# Sheet1.net
KiCad netlist of a schematic drawn in Altium Designer
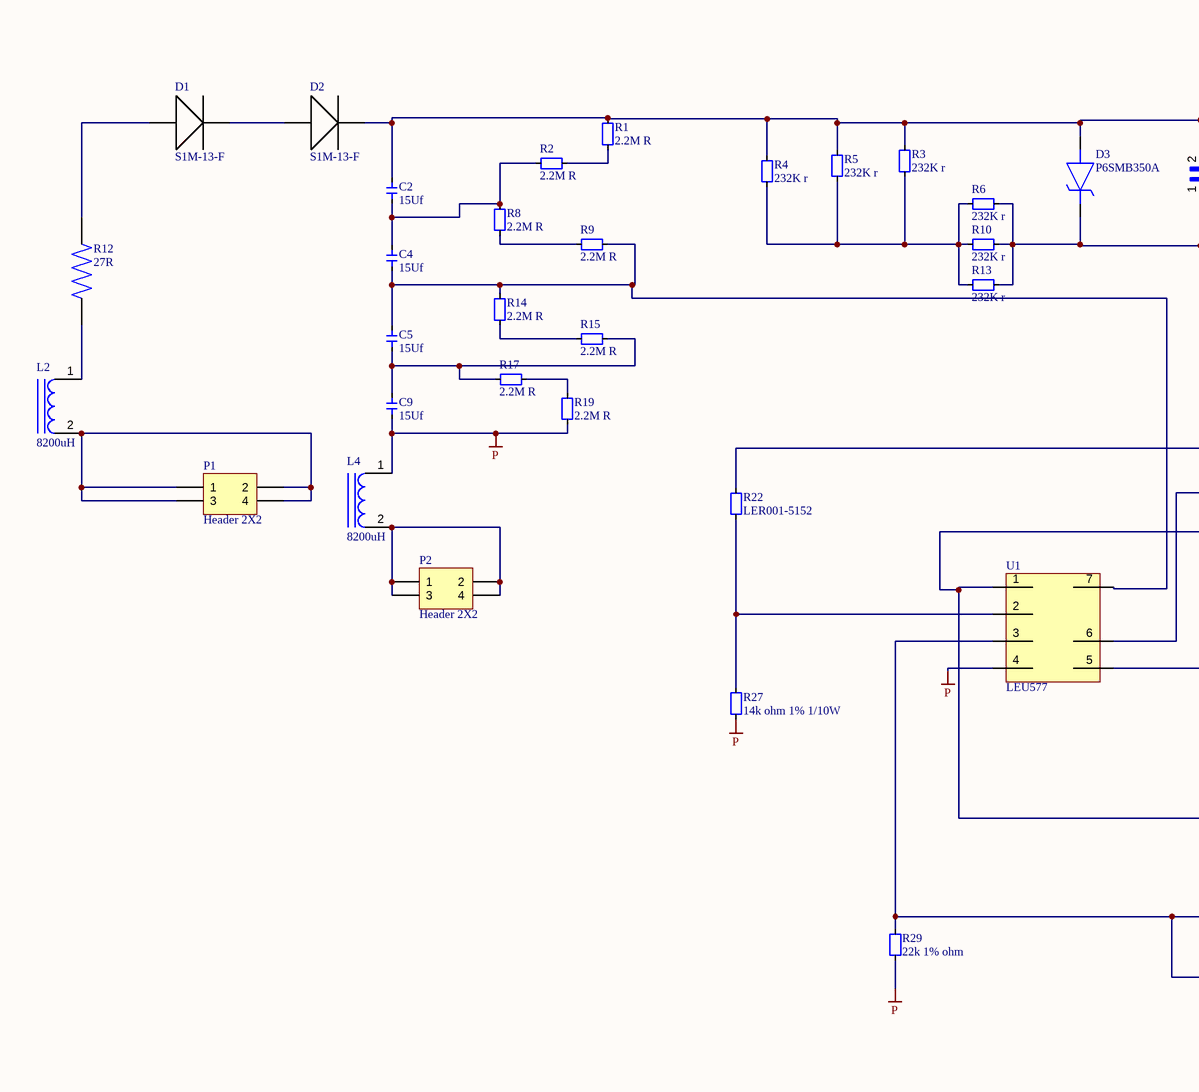
[diagram p0: Sheet1.SchDoc, left]
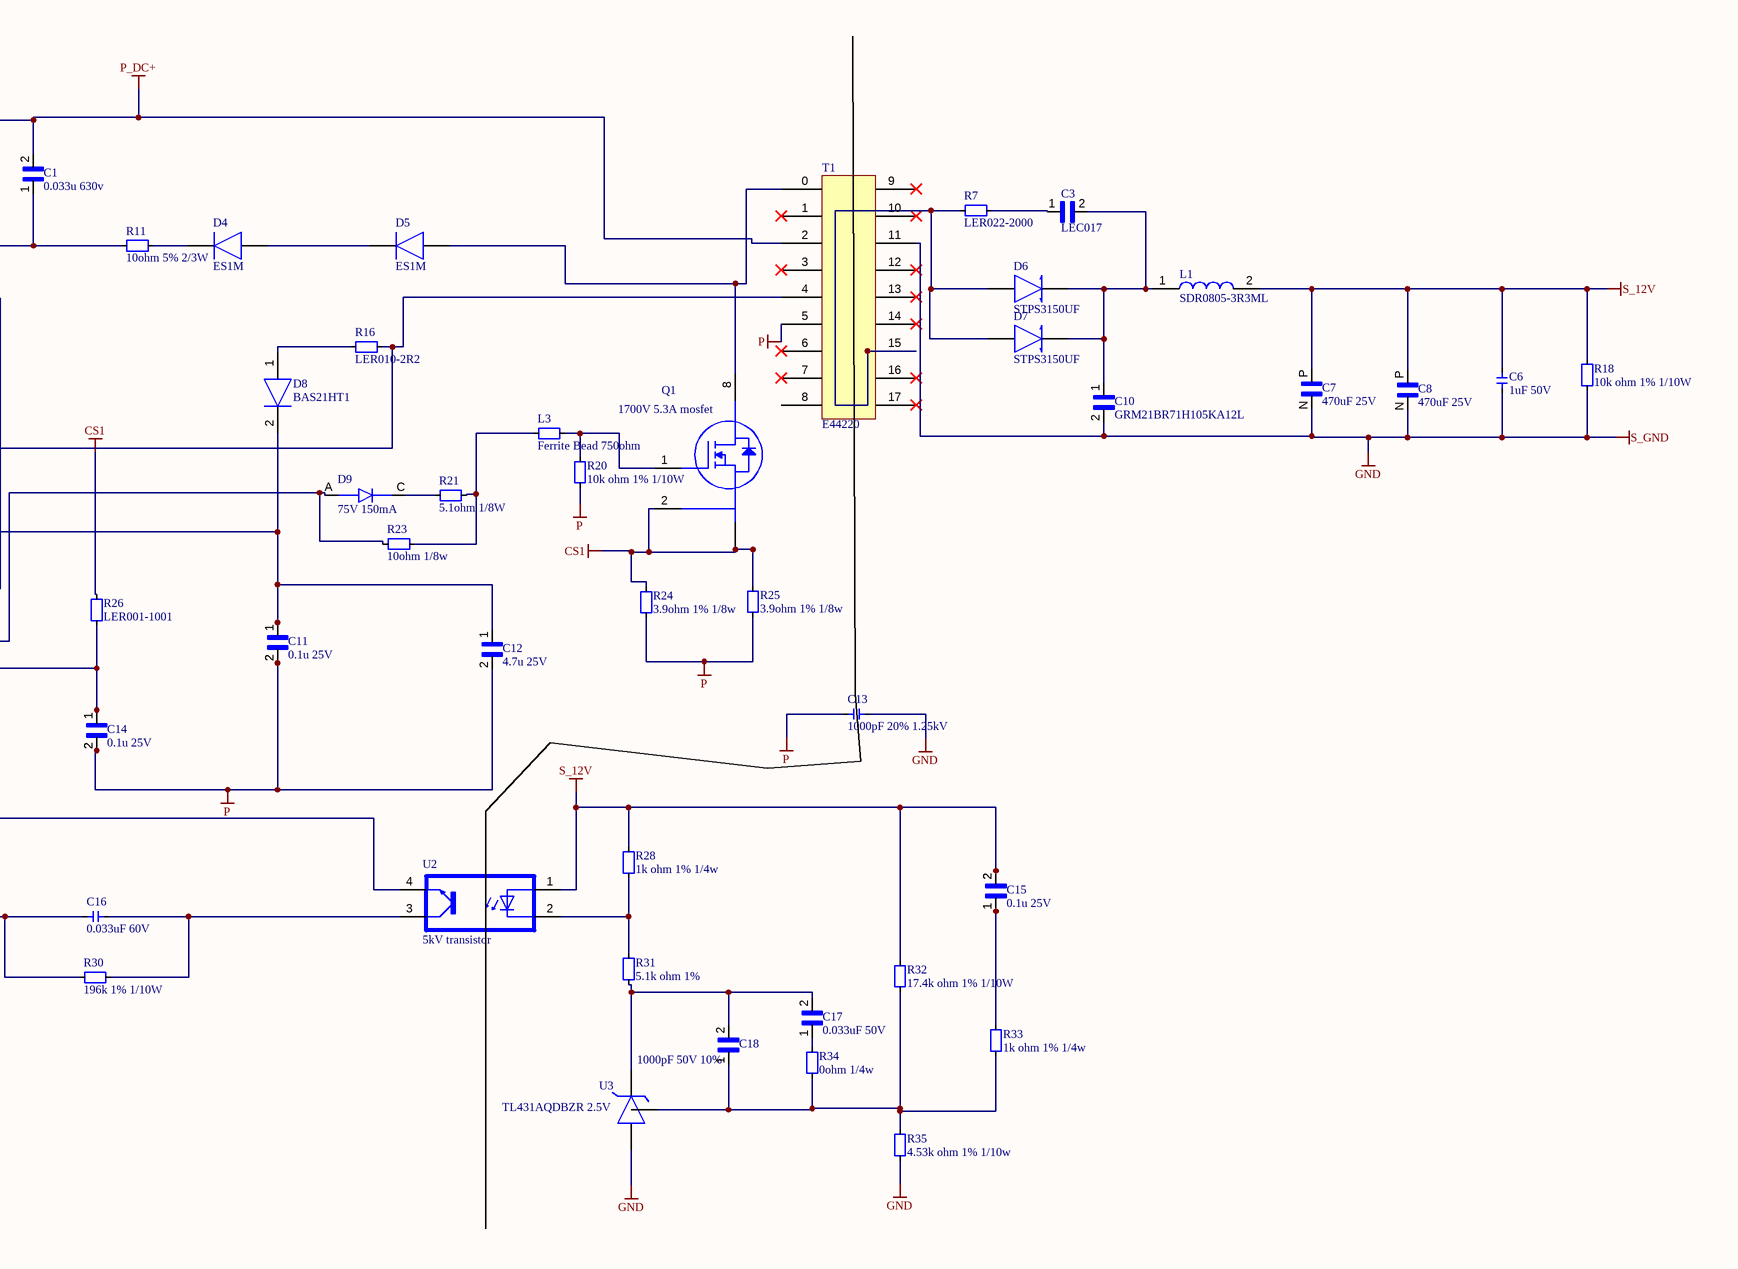
[diagram p1: Sheet1.SchDoc, right]

(export (version "E")
  (design (tool "Eeschema 10.0.6"))
  (components
    (comp (ref "C1")
      (value "0.033u 630v")
      (footprint "PcbLib1:0.33u 630V c")
      (libsource (lib "Schlib1") (part "0.033u 630v"))
    )
    (comp (ref "C2") (value "15Uf") (footprint "PcbLib1:15uf") (libsource (lib "Schlib1") (part "15Uf")))
    (comp (ref "C3")
      (value "LEC017")
      (footprint "PcbLib1:LEC017")
      (libsource (lib "Schlib1") (part "LEC017"))
    )
    (comp (ref "C4") (value "15Uf") (footprint "PcbLib1:15uf") (libsource (lib "Schlib1") (part "15Uf")))
    (comp (ref "C5") (value "15Uf") (footprint "PcbLib1:15uf") (libsource (lib "Schlib1") (part "15Uf")))
    (comp (ref "C6")
      (value "1uF 50V")
      (footprint "PcbLib1:C-0805")
      (libsource (lib "Schlib1") (part "1uF 50V"))
    )
    (comp (ref "C7")
      (value "470uF 25V")
      (footprint "470uF 25V")
      (libsource (lib "Schlib1") (part "470uF 25V"))
    )
    (comp (ref "C8")
      (value "470uF 25V")
      (footprint "470uF 25V")
      (libsource (lib "Schlib1") (part "470uF 25V"))
    )
    (comp (ref "C9") (value "15Uf") (footprint "PcbLib1:15uf") (libsource (lib "Schlib1") (part "15Uf")))
    (comp (ref "C10")
      (value "GRM21BR71H105KA12L")
      (footprint "PcbLib1:CAPC2012X135N")
      (description "SMD Capacitor X7R(EIA) with Capacitance: 1.0uF Tol. 10%. Rated Voltage: 50Vdc")
      (fields (field (name "MF") "Murata"))
      (libsource (lib "Schlib1") (part "GRM21BR71H105KA12L"))
    )
    (comp (ref "C11")
      (value "0.1u 25V")
      (footprint "CAPC2012X135N")
      (libsource (lib "Schlib1") (part "0.1u 25V"))
    )
    (comp (ref "C12")
      (value "4.7u 25V")
      (footprint "PcbLib1:4.7u 25V")
      (libsource (lib "Schlib1") (part "4.7u 25V"))
    )
    (comp (ref "C13")
      (value "1000pF 20% 1.25kV")
      (footprint "PcbLib1:CAP Fılm 1000pF 20% 450V")
      (libsource (lib "Schlib1") (part "1000pF 20% 1.25kV"))
    )
    (comp (ref "C14")
      (value "0.1u 25V")
      (footprint "CAPC2012X135N")
      (libsource (lib "Schlib1") (part "0.1u 25V"))
    )
    (comp (ref "C15") (value "0.1u 25V") (footprint "CAPC2012X135N") (libsource (lib "") (part "0.1u 25V_1")))
    (comp (ref "C16")
      (value "0.033uF 60V")
      (footprint "PcbLib1:C-0603")
      (libsource (lib "Schlib1") (part "0.033uF 60V"))
    )
    (comp (ref "C17")
      (value "0.033uF 50V")
      (footprint "PcbLib1:C-0603")
      (libsource (lib "Schlib1") (part "0.033uF 50V"))
    )
    (comp (ref "C18")
      (value "1000pF 50V 10%")
      (footprint "PcbLib1:C-0805")
      (libsource (lib "Schlib1") (part "1000pF 50V 10%"))
    )
    (comp (ref "D1")
      (value "S1M-13-F")
      (footprint "PcbLib1:S1M-13F")
      (libsource (lib "Schlib1") (part "S1M-13-F"))
    )
    (comp (ref "D2")
      (value "S1M-13-F")
      (footprint "PcbLib1:S1M-13F")
      (libsource (lib "Schlib1") (part "S1M-13-F"))
    )
    (comp (ref "D3")
      (value "P6SMB350A")
      (footprint "PcbLib1:P6SMB350A")
      (libsource (lib "Schlib1") (part "P6SMB350A"))
    )
    (comp (ref "D4") (value "ES1M") (footprint "ES1M") (libsource (lib "Schlib1") (part "ES1M")))
    (comp (ref "D5") (value "ES1M") (footprint "ES1M") (libsource (lib "Schlib1") (part "ES1M")))
    (comp (ref "D6")
      (value "STPS3150UF")
      (footprint "PcbLib1:STPS3150UF")
      (libsource (lib "Schlib1") (part "STPS3150UF"))
    )
    (comp (ref "D7")
      (value "STPS3150UF")
      (footprint "PcbLib1:STPS3150UF")
      (libsource (lib "Schlib1") (part "STPS3150UF"))
    )
    (comp (ref "D8")
      (value "BAS21HT1")
      (footprint "PcbLib1:BAS21HT1")
      (libsource (lib "Schlib1") (part "BAS21HT1"))
    )
    (comp (ref "D9")
      (value "75V 150mA")
      (footprint "PcbLib1:75V 150mA")
      (libsource (lib "Schlib1") (part "75V 150mA"))
    )
    (comp (ref "L1")
      (value "SDR0805-3R3ML")
      (footprint "PcbLib1:8200uH")
      (libsource (lib "Schlib1") (part "SDR0805-3R3ML"))
    )
    (comp (ref "L2")
      (value "8200uH")
      (footprint "PcbLib1:8200uH")
      (libsource (lib "Schlib1") (part "8200uH"))
    )
    (comp (ref "L3")
      (value "Ferrite Bead 750ohm")
      (footprint "PcbLib1:Ferrite Bead 750ohm")
      (libsource (lib "Schlib1") (part "Ferrite Bead 750ohm"))
    )
    (comp (ref "L4")
      (value "8200uH")
      (footprint "PcbLib1:8200uH")
      (libsource (lib "Schlib1") (part "8200uH"))
    )
    (comp (ref "P1")
      (value "Header 2X2")
      (footprint "HDR2X2")
      (description "Header, 2-Pin, Dual row")
      (fields (field (name "PUBLISHER") "Altium Limited"))
      (libsource (lib "Miscellaneous Connectors") (part "Header 2X2"))
    )
    (comp (ref "P2")
      (value "Header 2X2")
      (footprint "HDR2X2")
      (description "Header, 2-Pin, Dual row")
      (fields (field (name "PUBLISHER") "Altium Limited"))
      (libsource (lib "Miscellaneous Connectors") (part "Header 2X2"))
    )
    (comp (ref "Q1")
      (value "1700V 5.3A mosfet")
      (footprint "PcbLib1:1400V 5.3A Mosfet")
      (libsource (lib "Schlib1") (part "1700V 5.3A mosfet"))
    )
    (comp (ref "R1") (value "2.2M R") (footprint "PcbLib1:232K") (libsource (lib "Schlib1") (part "2.2M R")))
    (comp (ref "R2") (value "2.2M R") (footprint "PcbLib1:232K") (libsource (lib "Schlib1") (part "2.2M R")))
    (comp (ref "R3") (value "232K r") (footprint "232K") (libsource (lib "Schlib1") (part "232K r")))
    (comp (ref "R4") (value "232K r") (footprint "232K") (libsource (lib "Schlib1") (part "232K r")))
    (comp (ref "R5") (value "232K r") (footprint "232K") (libsource (lib "Schlib1") (part "232K r")))
    (comp (ref "R6") (value "232K r") (footprint "232K") (libsource (lib "Schlib1") (part "232K r")))
    (comp (ref "R7")
      (value "LER022-2000")
      (footprint "PcbLib1:LER022")
      (libsource (lib "Schlib1") (part "LER022-2000"))
    )
    (comp (ref "R8") (value "2.2M R") (footprint "PcbLib1:232K") (libsource (lib "Schlib1") (part "2.2M R")))
    (comp (ref "R9") (value "2.2M R") (footprint "PcbLib1:232K") (libsource (lib "Schlib1") (part "2.2M R")))
    (comp (ref "R10") (value "232K r") (footprint "232K") (libsource (lib "Schlib1") (part "232K r")))
    (comp (ref "R11")
      (value "10ohm 5% 2/3W")
      (footprint "PcbLib1:10 ohm %5")
      (libsource (lib "Schlib1") (part "10ohm 5% 2/3W"))
    )
    (comp (ref "R12") (value "27R") (footprint "PcbLib1:75R2W") (libsource (lib "Schlib1") (part "27R")))
    (comp (ref "R13") (value "232K r") (footprint "232K") (libsource (lib "Schlib1") (part "232K r")))
    (comp (ref "R14") (value "2.2M R") (footprint "PcbLib1:232K") (libsource (lib "Schlib1") (part "2.2M R")))
    (comp (ref "R15") (value "2.2M R") (footprint "PcbLib1:232K") (libsource (lib "Schlib1") (part "2.2M R")))
    (comp (ref "R16")
      (value "LER010-2R2")
      (footprint "PcbLib1:LER010-2R2")
      (libsource (lib "Schlib1") (part "LER010-2R2"))
    )
    (comp (ref "R17") (value "2.2M R") (footprint "PcbLib1:232K") (libsource (lib "Schlib1") (part "2.2M R")))
    (comp (ref "R18")
      (value "10k ohm 1% 1/10W")
      (footprint "PcbLib1:10k ohm 1%")
      (libsource (lib "Schlib1") (part "10k ohm 1% 1/10W"))
    )
    (comp (ref "R19") (value "2.2M R") (footprint "PcbLib1:232K") (libsource (lib "Schlib1") (part "2.2M R")))
    (comp (ref "R20")
      (value "10k ohm 1% 1/10W")
      (footprint "PcbLib1:10k ohm 1%")
      (libsource (lib "Schlib1") (part "10k ohm 1% 1/10W"))
    )
    (comp (ref "R21")
      (value "5.1ohm 1/8W")
      (footprint "PcbLib1:5.1 ohm 1/8w")
      (libsource (lib "Schlib1") (part "5.1ohm 1/8W"))
    )
    (comp (ref "R22")
      (value "LER001-5152")
      (footprint "PcbLib1:LER001-5152")
      (libsource (lib "Schlib1") (part "LER001-5152"))
    )
    (comp (ref "R23")
      (value "10ohm 1/8w")
      (footprint "PcbLib1:5.1 ohm 1/8w")
      (libsource (lib "Schlib1") (part "10ohm 1/8w"))
    )
    (comp (ref "R24")
      (value "3.9ohm 1% 1/8w")
      (footprint "PcbLib1:5.1 ohm 1/8w")
      (libsource (lib "Schlib1") (part "3.9ohm 1% 1/8w"))
    )
    (comp (ref "R25")
      (value "3.9ohm 1% 1/8w")
      (footprint "PcbLib1:5.1 ohm 1/8w")
      (libsource (lib "Schlib1") (part "3.9ohm 1% 1/8w"))
    )
    (comp (ref "R26")
      (value "LER001-1001")
      (footprint "PcbLib1:LER001-1001")
      (libsource (lib "Schlib1") (part "LER001-1001"))
    )
    (comp (ref "R27")
      (value "14k ohm 1% 1/10W")
      (footprint "PcbLib1:R-0603")
      (libsource (lib "Schlib1") (part "14k ohm 1% 1/10W"))
    )
    (comp (ref "R28")
      (value "1k ohm 1% 1/4w")
      (footprint "PcbLib1:R-0603")
      (libsource (lib "Schlib1") (part "1k ohm 1% 1/4w"))
    )
    (comp (ref "R29")
      (value "22k 1% ohm")
      (footprint "PcbLib1:R-0603")
      (libsource (lib "Schlib1") (part "22k 1% ohm"))
    )
    (comp (ref "R30")
      (value "196k 1% 1/10W")
      (footprint "PcbLib1:R-0603")
      (libsource (lib "Schlib1") (part "196k 1% 1/10W"))
    )
    (comp (ref "R31")
      (value "5.1k ohm 1%")
      (footprint "PcbLib1:R-0603")
      (libsource (lib "Schlib1") (part "5.1k ohm 1%"))
    )
    (comp (ref "R32")
      (value "17.4k ohm 1% 1/10W")
      (footprint "PcbLib1:R-0603")
      (libsource (lib "Schlib1") (part "17.4k ohm 1% 1/10W"))
    )
    (comp (ref "R33")
      (value "1k ohm 1% 1/4w")
      (footprint "PcbLib1:R-0603")
      (libsource (lib "Schlib1") (part "1k ohm 1% 1/4w"))
    )
    (comp (ref "R34")
      (value "0ohm 1/4w")
      (footprint "PcbLib1:R-0603")
      (libsource (lib "Schlib1") (part "0ohm 1/4w"))
    )
    (comp (ref "R35")
      (value "4.53k ohm 1% 1/10w")
      (footprint "PcbLib1:R-0603")
      (libsource (lib "Schlib1") (part "4.53k ohm 1% 1/10w"))
    )
    (comp (ref "T1")
      (value "E44220")
      (footprint "PcbLib1:E44220")
      (libsource (lib "Schlib1") (part "E44220"))
    )
    (comp (ref "U1")
      (value "LEU577")
      (footprint "PcbLib1:LEU577")
      (libsource (lib "Schlib1") (part "LEU577"))
    )
    (comp (ref "U2")
      (value "5kV transistor")
      (footprint "PcbLib1:SOP-4")
      (libsource (lib "Schlib1") (part "5kV transistor"))
    )
    (comp (ref "U3")
      (value "TL431AQDBZR 2.5V")
      (footprint "PcbLib1:SOT95P237X112-3N")
      (libsource (lib "Schlib1") (part "TL431AQDBZR 2.5V"))
    )
  )
  (nets
    (net (code "1") (name "CS1") (class "Default")
      (node (ref "Q1") (pin "2") (pinfunction "DRIVER_SOURCE_2") (pintype "passive"))
      (node (ref "Q1") (pin "3") (pinfunction "POWER_SOURCE_3") (pintype "passive"))
      (node (ref "Q1") (pin "4") (pinfunction "POWER_SOURCE_4") (pintype "passive"))
      (node (ref "Q1") (pin "5") (pinfunction "POWER_SOURCE_5") (pintype "passive"))
      (node (ref "Q1") (pin "6") (pinfunction "POWER_SOURCE_6") (pintype "passive"))
      (node (ref "Q1") (pin "7") (pinfunction "POWER_SOURCE_7") (pintype "passive"))
      (node (ref "R24") (pin "2") (pinfunction "2_2") (pintype "passive"))
      (node (ref "R25") (pin "2") (pinfunction "2_2") (pintype "passive"))
      (node (ref "R26") (pin "2") (pinfunction "2_2") (pintype "passive"))
    )
    (net (code "2") (name "GND") (class "Default")
      (node (ref "C10") (pin "2") (pinfunction "2_2") (pintype "passive"))
      (node (ref "C13") (pin "2") (pinfunction "2_2") (pintype "passive"))
      (node (ref "C6") (pin "2") (pinfunction "2_2") (pintype "passive"))
      (node (ref "C7") (pin "N") (pinfunction "1_N") (pintype "passive"))
      (node (ref "C8") (pin "N") (pinfunction "1_N") (pintype "passive"))
      (node (ref "R18") (pin "1") (pinfunction "1_1") (pintype "passive"))
      (node (ref "R35") (pin "1") (pinfunction "1_1") (pintype "passive"))
      (node (ref "T1") (pin "11") (pinfunction "11_11") (pintype "passive"))
      (node (ref "U3") (pin "1") (pinfunction "1_1") (pintype "passive"))
    )
    (net (code "3") (name "Net-(C2-PadP)") (class "Default")
      (node (ref "C2") (pin "P") (pinfunction "P_P") (pintype "passive"))
      (node (ref "C4") (pin "N") (pinfunction "N_N") (pintype "passive"))
      (node (ref "R2") (pin "2") (pinfunction "2_2") (pintype "passive"))
      (node (ref "R8") (pin "1") (pinfunction "1_1") (pintype "passive"))
    )
    (net (code "4") (name "Net-(C3-Pad1)") (class "Default")
      (node (ref "C3") (pin "1") (pinfunction "1_1") (pintype "passive"))
      (node (ref "R7") (pin "2") (pinfunction "2_2") (pintype "passive"))
    )
    (net (code "5") (name "Net-(C4-PadP)") (class "Default")
      (node (ref "C4") (pin "P") (pinfunction "P_P") (pintype "passive"))
      (node (ref "C5") (pin "N") (pinfunction "N_N") (pintype "passive"))
      (node (ref "R14") (pin "2") (pinfunction "2_2") (pintype "passive"))
      (node (ref "R9") (pin "1") (pinfunction "1_1") (pintype "passive"))
      (node (ref "U1") (pin "7") (pinfunction "7_7") (pintype "passive"))
    )
    (net (code "6") (name "Net-(C5-PadP)") (class "Default")
      (node (ref "C5") (pin "P") (pinfunction "P_P") (pintype "passive"))
      (node (ref "C9") (pin "N") (pinfunction "N_N") (pintype "passive"))
      (node (ref "R15") (pin "1") (pinfunction "1_1") (pintype "passive"))
      (node (ref "R17") (pin "2") (pinfunction "2_2") (pintype "passive"))
    )
    (net (code "7") (name "Net-(C14-Pad1)") (class "Default")
      (node (ref "C14") (pin "1") (pinfunction "1_1") (pintype "passive"))
      (node (ref "R26") (pin "1") (pinfunction "1_1") (pintype "passive"))
      (node (ref "U1") (pin "5") (pinfunction "5_5") (pintype "passive"))
    )
    (net (code "8") (name "Net-(C15-Pad1)") (class "Default")
      (node (ref "C15") (pin "1") (pinfunction "1_1") (pintype "passive"))
      (node (ref "R33") (pin "2") (pinfunction "2_2") (pintype "passive"))
    )
    (net (code "9") (name "Net-(C16-Pad1)") (class "Default")
      (node (ref "C16") (pin "1") (pinfunction "1_1") (pintype "passive"))
      (node (ref "R29") (pin "2") (pinfunction "2_2") (pintype "passive"))
      (node (ref "R30") (pin "1") (pinfunction "1_1") (pintype "passive"))
      (node (ref "U1") (pin "3") (pinfunction "3_3") (pintype "passive"))
    )
    (net (code "10") (name "Net-(C17-Pad1)") (class "Default")
      (node (ref "C17") (pin "1") (pinfunction "1_1") (pintype "passive"))
      (node (ref "R34") (pin "2") (pinfunction "2_2") (pintype "passive"))
    )
    (net (code "11") (name "Net-(C17-Pad2)") (class "Default")
      (node (ref "C17") (pin "2") (pinfunction "2_2") (pintype "passive"))
      (node (ref "C18") (pin "2") (pinfunction "2_2") (pintype "passive"))
      (node (ref "R31") (pin "1") (pinfunction "1_1") (pintype "passive"))
      (node (ref "U3") (pin "3") (pinfunction "3_3") (pintype "passive"))
    )
    (net (code "12") (name "Net-(C18-Pad1)") (class "Default")
      (node (ref "C18") (pin "1") (pinfunction "1_1") (pintype "passive"))
      (node (ref "R32") (pin "1") (pinfunction "1_1") (pintype "passive"))
      (node (ref "R33") (pin "1") (pinfunction "1_1") (pintype "passive"))
      (node (ref "R34") (pin "1") (pinfunction "1_1") (pintype "passive"))
      (node (ref "R35") (pin "2") (pinfunction "2_2") (pintype "passive"))
      (node (ref "U3") (pin "2") (pinfunction "2_2") (pintype "passive"))
    )
    (net (code "13") (name "Net-(D1-PadA)") (class "Default")
      (node (ref "D1") (pin "A") (pinfunction "A_A") (pintype "passive"))
      (node (ref "D2") (pin "C") (pinfunction "C_C") (pintype "passive"))
    )
    (net (code "14") (name "Net-(D1-PadC)") (class "Default")
      (node (ref "D1") (pin "C") (pinfunction "C_C") (pintype "passive"))
      (node (ref "R12") (pin "2") (pinfunction "2_2") (pintype "passive"))
    )
    (net (code "15") (name "Net-(D3-K)") (class "Default")
      (node (ref "C1") (pin "1") (pinfunction "1_1") (pintype "passive"))
      (node (ref "D3") (pin "C") (pinfunction "K_C") (pintype "passive"))
      (node (ref "R10") (pin "1") (pinfunction "1_1") (pintype "passive"))
      (node (ref "R11") (pin "1") (pinfunction "1_1") (pintype "passive"))
      (node (ref "R13") (pin "1") (pinfunction "1_1") (pintype "passive"))
      (node (ref "R6") (pin "1") (pinfunction "1_1") (pintype "passive"))
    )
    (net (code "16") (name "Net-(D4-PadA)") (class "Default")
      (node (ref "D4") (pin "A") (pinfunction "A_A") (pintype "passive"))
      (node (ref "D5") (pin "C") (pinfunction "C_C") (pintype "passive"))
    )
    (net (code "17") (name "Net-(D4-PadC)") (class "Default")
      (node (ref "D4") (pin "C") (pinfunction "C_C") (pintype "passive"))
      (node (ref "R11") (pin "2") (pinfunction "2_2") (pintype "passive"))
    )
    (net (code "18") (name "Net-(D6-K)") (class "Default")
      (node (ref "C10") (pin "1") (pinfunction "1_1") (pintype "passive"))
      (node (ref "C3") (pin "2") (pinfunction "2_2") (pintype "passive"))
      (node (ref "D6") (pin "C") (pinfunction "K_C") (pintype "passive"))
      (node (ref "D7") (pin "C") (pinfunction "K_C") (pintype "passive"))
      (node (ref "L1") (pin "1") (pinfunction "1_1") (pintype "passive"))
    )
    (net (code "19") (name "Net-(D6-PadA)") (class "Default")
      (node (ref "D6") (pin "A") (pinfunction "A_A") (pintype "passive"))
      (node (ref "D7") (pin "A") (pinfunction "A_A") (pintype "passive"))
      (node (ref "R7") (pin "1") (pinfunction "1_1") (pintype "passive"))
      (node (ref "T1") (pin "15") (pinfunction "15_15") (pintype "passive"))
    )
    (net (code "20") (name "Net-(D8-A)") (class "Default")
      (node (ref "D8") (pin "1") (pinfunction "A_1") (pintype "passive"))
      (node (ref "R16") (pin "1") (pinfunction "1_1") (pintype "passive"))
    )
    (net (code "21") (name "Net-(D8-K)") (class "Default")
      (node (ref "C11") (pin "1") (pinfunction "1_1") (pintype "passive"))
      (node (ref "C12") (pin "1") (pinfunction "1_1") (pintype "passive"))
      (node (ref "D8") (pin "2") (pinfunction "K_2") (pintype "passive"))
      (node (ref "U1") (pin "1") (pinfunction "1_1") (pintype "passive"))
      (node (ref "U2") (pin "4") (pinfunction "CO_4") (pintype "passive"))
    )
    (net (code "22") (name "Net-(D9-PadA)") (class "Default")
      (node (ref "D9") (pin "A") (pinfunction "A_A") (pintype "passive"))
      (node (ref "R23") (pin "1") (pinfunction "1_1") (pintype "passive"))
      (node (ref "U1") (pin "6") (pinfunction "6_6") (pintype "passive"))
    )
    (net (code "23") (name "Net-(D9-PadC)") (class "Default")
      (node (ref "D9") (pin "C") (pinfunction "C_C") (pintype "passive"))
      (node (ref "R21") (pin "2") (pinfunction "2_2") (pintype "passive"))
    )
    (net (code "24") (name "Net-(L2-Pad1)") (class "Default")
      (node (ref "L2") (pin "1") (pinfunction "1_1") (pintype "passive"))
      (node (ref "R12") (pin "1") (pinfunction "1_1") (pintype "passive"))
    )
    (net (code "25") (name "Net-(L2-Pad2)") (class "Default")
      (node (ref "L2") (pin "2") (pinfunction "2_2") (pintype "passive"))
      (node (ref "P1") (pin "1") (pinfunction "1_1") (pintype "passive"))
      (node (ref "P1") (pin "2") (pinfunction "2_2") (pintype "passive"))
      (node (ref "P1") (pin "3") (pinfunction "3_3") (pintype "passive"))
      (node (ref "P1") (pin "4") (pinfunction "4_4") (pintype "passive"))
    )
    (net (code "26") (name "Net-(L3-Pad1)") (class "Default")
      (node (ref "L3") (pin "1") (pinfunction "1_1") (pintype "passive"))
      (node (ref "R21") (pin "1") (pinfunction "1_1") (pintype "passive"))
      (node (ref "R23") (pin "2") (pinfunction "2_2") (pintype "passive"))
    )
    (net (code "27") (name "Net-(L4-Pad2)") (class "Default")
      (node (ref "L4") (pin "2") (pinfunction "2_2") (pintype "passive"))
      (node (ref "P2") (pin "1") (pinfunction "1_1") (pintype "passive"))
      (node (ref "P2") (pin "2") (pinfunction "2_2") (pintype "passive"))
      (node (ref "P2") (pin "3") (pinfunction "3_3") (pintype "passive"))
      (node (ref "P2") (pin "4") (pinfunction "4_4") (pintype "passive"))
    )
    (net (code "28") (name "Net-(Q1-DRAIN)") (class "Default")
      (node (ref "D5") (pin "A") (pinfunction "A_A") (pintype "passive"))
      (node (ref "Q1") (pin "8") (pinfunction "DRAIN_8") (pintype "passive"))
      (node (ref "T1") (pin "0") (pinfunction "0_0") (pintype "passive"))
    )
    (net (code "29") (name "Net-(Q1-GATE)") (class "Default")
      (node (ref "L3") (pin "2") (pinfunction "2_2") (pintype "passive"))
      (node (ref "Q1") (pin "1") (pinfunction "GATE_1") (pintype "passive"))
      (node (ref "R20") (pin "2") (pinfunction "2_2") (pintype "passive"))
    )
    (net (code "30") (name "Net-(R1-Pad1)") (class "Default")
      (node (ref "R1") (pin "1") (pinfunction "1_1") (pintype "passive"))
      (node (ref "R2") (pin "1") (pinfunction "1_1") (pintype "passive"))
    )
    (net (code "31") (name "Net-(R8-Pad2)") (class "Default")
      (node (ref "R8") (pin "2") (pinfunction "2_2") (pintype "passive"))
      (node (ref "R9") (pin "2") (pinfunction "2_2") (pintype "passive"))
    )
    (net (code "32") (name "Net-(R10-Pad2)") (class "Default")
      (node (ref "R10") (pin "2") (pinfunction "2_2") (pintype "passive"))
      (node (ref "R13") (pin "2") (pinfunction "2_2") (pintype "passive"))
      (node (ref "R3") (pin "1") (pinfunction "1_1") (pintype "passive"))
      (node (ref "R4") (pin "1") (pinfunction "1_1") (pintype "passive"))
      (node (ref "R5") (pin "1") (pinfunction "1_1") (pintype "passive"))
      (node (ref "R6") (pin "2") (pinfunction "2_2") (pintype "passive"))
    )
    (net (code "33") (name "Net-(R14-Pad1)") (class "Default")
      (node (ref "R14") (pin "1") (pinfunction "1_1") (pintype "passive"))
      (node (ref "R15") (pin "2") (pinfunction "2_2") (pintype "passive"))
    )
    (net (code "34") (name "Net-(R16-Pad2)") (class "Default")
      (node (ref "R16") (pin "2") (pinfunction "2_2") (pintype "passive"))
      (node (ref "R22") (pin "2") (pinfunction "2_2") (pintype "passive"))
      (node (ref "T1") (pin "4") (pinfunction "4_4") (pintype "passive"))
    )
    (net (code "35") (name "Net-(R17-Pad1)") (class "Default")
      (node (ref "R17") (pin "1") (pinfunction "1_1") (pintype "passive"))
      (node (ref "R19") (pin "1") (pinfunction "1_1") (pintype "passive"))
    )
    (net (code "36") (name "Net-(R22-Pad1)") (class "Default")
      (node (ref "R22") (pin "1") (pinfunction "1_1") (pintype "passive"))
      (node (ref "R27") (pin "2") (pinfunction "2_2") (pintype "passive"))
      (node (ref "U1") (pin "2") (pinfunction "2_2") (pintype "passive"))
    )
    (net (code "37") (name "Net-(U2-C)") (class "Default")
      (node (ref "R28") (pin "1") (pinfunction "1_1") (pintype "passive"))
      (node (ref "R31") (pin "2") (pinfunction "2_2") (pintype "passive"))
      (node (ref "U2") (pin "2") (pinfunction "C_2") (pintype "passive"))
    )
    (net (code "38") (name "Net-(U2-E)") (class "Default")
      (node (ref "C16") (pin "2") (pinfunction "2_2") (pintype "passive"))
      (node (ref "R30") (pin "2") (pinfunction "2_2") (pintype "passive"))
      (node (ref "U2") (pin "3") (pinfunction "E_3") (pintype "passive"))
    )
    (net (code "39") (name "P") (class "Default")
      (node (ref "C11") (pin "2") (pinfunction "2_2") (pintype "passive"))
      (node (ref "C12") (pin "2") (pinfunction "2_2") (pintype "passive"))
      (node (ref "C13") (pin "1") (pinfunction "1_1") (pintype "passive"))
      (node (ref "C14") (pin "2") (pinfunction "2_2") (pintype "passive"))
      (node (ref "C9") (pin "P") (pinfunction "P_P") (pintype "passive"))
      (node (ref "L4") (pin "1") (pinfunction "1_1") (pintype "passive"))
      (node (ref "R19") (pin "2") (pinfunction "2_2") (pintype "passive"))
      (node (ref "R20") (pin "1") (pinfunction "1_1") (pintype "passive"))
      (node (ref "R24") (pin "1") (pinfunction "1_1") (pintype "passive"))
      (node (ref "R25") (pin "1") (pinfunction "1_1") (pintype "passive"))
      (node (ref "R27") (pin "1") (pinfunction "1_1") (pintype "passive"))
      (node (ref "R29") (pin "1") (pinfunction "1_1") (pintype "passive"))
      (node (ref "T1") (pin "5") (pinfunction "5_5") (pintype "passive"))
      (node (ref "U1") (pin "4") (pinfunction "4_4") (pintype "passive"))
    )
    (net (code "40") (name "P_DC+") (class "Default")
      (node (ref "C1") (pin "2") (pinfunction "2_2") (pintype "passive"))
      (node (ref "C2") (pin "N") (pinfunction "N_N") (pintype "passive"))
      (node (ref "D2") (pin "A") (pinfunction "A_A") (pintype "passive"))
      (node (ref "D3") (pin "A") (pinfunction "A_A") (pintype "passive"))
      (node (ref "R1") (pin "2") (pinfunction "2_2") (pintype "passive"))
      (node (ref "R3") (pin "2") (pinfunction "2_2") (pintype "passive"))
      (node (ref "R4") (pin "2") (pinfunction "2_2") (pintype "passive"))
      (node (ref "R5") (pin "2") (pinfunction "2_2") (pintype "passive"))
      (node (ref "T1") (pin "2") (pinfunction "2_2") (pintype "passive"))
    )
    (net (code "41") (name "S_12V") (class "Default")
      (node (ref "C15") (pin "2") (pinfunction "2_2") (pintype "passive"))
      (node (ref "C6") (pin "1") (pinfunction "1_1") (pintype "passive"))
      (node (ref "C7") (pin "P") (pinfunction "2_P") (pintype "passive"))
      (node (ref "C8") (pin "P") (pinfunction "2_P") (pintype "passive"))
      (node (ref "L1") (pin "2") (pinfunction "2_2") (pintype "passive"))
      (node (ref "R18") (pin "2") (pinfunction "2_2") (pintype "passive"))
      (node (ref "R28") (pin "2") (pinfunction "2_2") (pintype "passive"))
      (node (ref "R32") (pin "2") (pinfunction "2_2") (pintype "passive"))
      (node (ref "U2") (pin "1") (pinfunction "A_1") (pintype "passive"))
    )
    (net (code "42") (name "unconnected-(T1-7-Pad6)") (class "Default")
      (node (ref "T1") (pin "6") (pinfunction "7_6") (pintype "passive+no_connect"))
    )
    (net (code "43") (name "unconnected-(T1-Pad1)") (class "Default")
      (node (ref "T1") (pin "1") (pinfunction "1_1") (pintype "passive+no_connect"))
    )
    (net (code "44") (name "unconnected-(T1-Pad3)") (class "Default")
      (node (ref "T1") (pin "3") (pinfunction "3_3") (pintype "passive+no_connect"))
    )
    (net (code "45") (name "unconnected-(T1-Pad7)") (class "Default")
      (node (ref "T1") (pin "7") (pinfunction "7_7") (pintype "passive+no_connect"))
    )
    (net (code "46") (name "unconnected-(T1-Pad8)") (class "Default")
      (node (ref "T1") (pin "8") (pinfunction "8_8") (pintype "passive"))
    )
    (net (code "47") (name "unconnected-(T1-Pad9)") (class "Default")
      (node (ref "T1") (pin "9") (pinfunction "9_9") (pintype "passive+no_connect"))
    )
    (net (code "48") (name "unconnected-(T1-Pad10)") (class "Default")
      (node (ref "T1") (pin "10") (pinfunction "10_10") (pintype "passive+no_connect"))
    )
    (net (code "49") (name "unconnected-(T1-Pad12)") (class "Default")
      (node (ref "T1") (pin "12") (pinfunction "12_12") (pintype "passive+no_connect"))
    )
    (net (code "50") (name "unconnected-(T1-Pad13)") (class "Default")
      (node (ref "T1") (pin "13") (pinfunction "13_13") (pintype "passive+no_connect"))
    )
    (net (code "51") (name "unconnected-(T1-Pad14)") (class "Default")
      (node (ref "T1") (pin "14") (pinfunction "14_14") (pintype "passive+no_connect"))
    )
    (net (code "52") (name "unconnected-(T1-Pad16)") (class "Default")
      (node (ref "T1") (pin "16") (pinfunction "16_16") (pintype "passive+no_connect"))
    )
    (net (code "53") (name "unconnected-(T1-Pad17)") (class "Default")
      (node (ref "T1") (pin "17") (pinfunction "17_17") (pintype "passive+no_connect"))
    )
  )
)
